# split4.net
KiCad netlist of a schematic drawn in Altium Designer
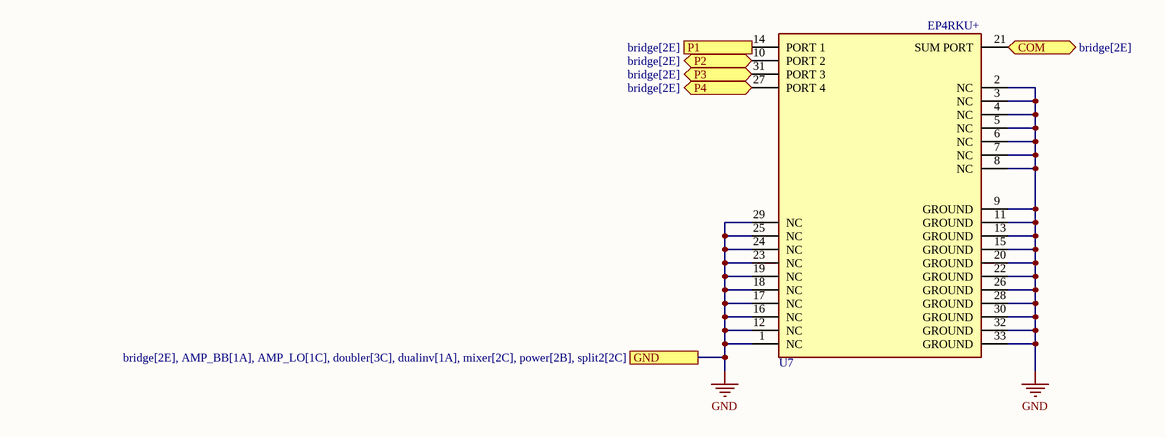
[diagram p0: split4.SchDoc]

(export (version "E")
  (design (tool "Eeschema 10.0.6"))
  (components
    (comp (ref "U7")
      (value "EP4RKU+")
      (footprint "EP4RKU+")
      (description "Power Splitter/Combiner 4 Way-0° 50Ω DC to 18 GHz")
      (fields (field (name "MANUFACTURER") "Mini-Circuits"))
      (libsource (lib "FullyDigital") (part "EP4RKU+"))
    )
  )
  (nets
    (net (code "1") (name "/COM") (class "Default")
      (node (ref "U7") (pin "21") (pinfunction "SUM_PORT_21") (pintype "passive"))
    )
    (net (code "2") (name "/P1") (class "Default")
      (node (ref "U7") (pin "14") (pinfunction "PORT_1_14") (pintype "passive"))
    )
    (net (code "3") (name "/P2") (class "Default")
      (node (ref "U7") (pin "10") (pinfunction "PORT_2_10") (pintype "passive"))
    )
    (net (code "4") (name "/P3") (class "Default")
      (node (ref "U7") (pin "31") (pinfunction "PORT_3_31") (pintype "passive"))
    )
    (net (code "5") (name "/P4") (class "Default")
      (node (ref "U7") (pin "27") (pinfunction "PORT_4_27") (pintype "passive"))
    )
    (net (code "6") (name "GND") (class "Default")
      (node (ref "U7") (pin "1") (pinfunction "NC_1") (pintype "passive"))
      (node (ref "U7") (pin "11") (pinfunction "GROUND_11") (pintype "power_in"))
      (node (ref "U7") (pin "12") (pinfunction "NC_12") (pintype "passive"))
      (node (ref "U7") (pin "13") (pinfunction "GROUND_13") (pintype "power_in"))
      (node (ref "U7") (pin "15") (pinfunction "GROUND_15") (pintype "power_in"))
      (node (ref "U7") (pin "16") (pinfunction "NC_16") (pintype "passive"))
      (node (ref "U7") (pin "17") (pinfunction "NC_17") (pintype "passive"))
      (node (ref "U7") (pin "18") (pinfunction "NC_18") (pintype "passive"))
      (node (ref "U7") (pin "19") (pinfunction "NC_19") (pintype "passive"))
      (node (ref "U7") (pin "2") (pinfunction "NC_2") (pintype "passive"))
      (node (ref "U7") (pin "20") (pinfunction "GROUND_20") (pintype "power_in"))
      (node (ref "U7") (pin "22") (pinfunction "GROUND_22") (pintype "power_in"))
      (node (ref "U7") (pin "23") (pinfunction "NC_23") (pintype "passive"))
      (node (ref "U7") (pin "24") (pinfunction "NC_24") (pintype "passive"))
      (node (ref "U7") (pin "25") (pinfunction "NC_25") (pintype "passive"))
      (node (ref "U7") (pin "26") (pinfunction "GROUND_26") (pintype "power_in"))
      (node (ref "U7") (pin "28") (pinfunction "GROUND_28") (pintype "power_in"))
      (node (ref "U7") (pin "29") (pinfunction "NC_29") (pintype "passive"))
      (node (ref "U7") (pin "3") (pinfunction "NC_3") (pintype "passive"))
      (node (ref "U7") (pin "30") (pinfunction "GROUND_30") (pintype "power_in"))
      (node (ref "U7") (pin "32") (pinfunction "GROUND_32") (pintype "power_in"))
      (node (ref "U7") (pin "33") (pinfunction "GROUND_33") (pintype "power_in"))
      (node (ref "U7") (pin "4") (pinfunction "NC_4") (pintype "passive"))
      (node (ref "U7") (pin "5") (pinfunction "NC_5") (pintype "passive"))
      (node (ref "U7") (pin "6") (pinfunction "NC_6") (pintype "passive"))
      (node (ref "U7") (pin "7") (pinfunction "NC_7") (pintype "passive"))
      (node (ref "U7") (pin "8") (pinfunction "NC_8") (pintype "passive"))
      (node (ref "U7") (pin "9") (pinfunction "GROUND_9") (pintype "power_in"))
    )
  )
)
